# schemantic.net
KiCad netlist of a schematic drawn in EAGLE
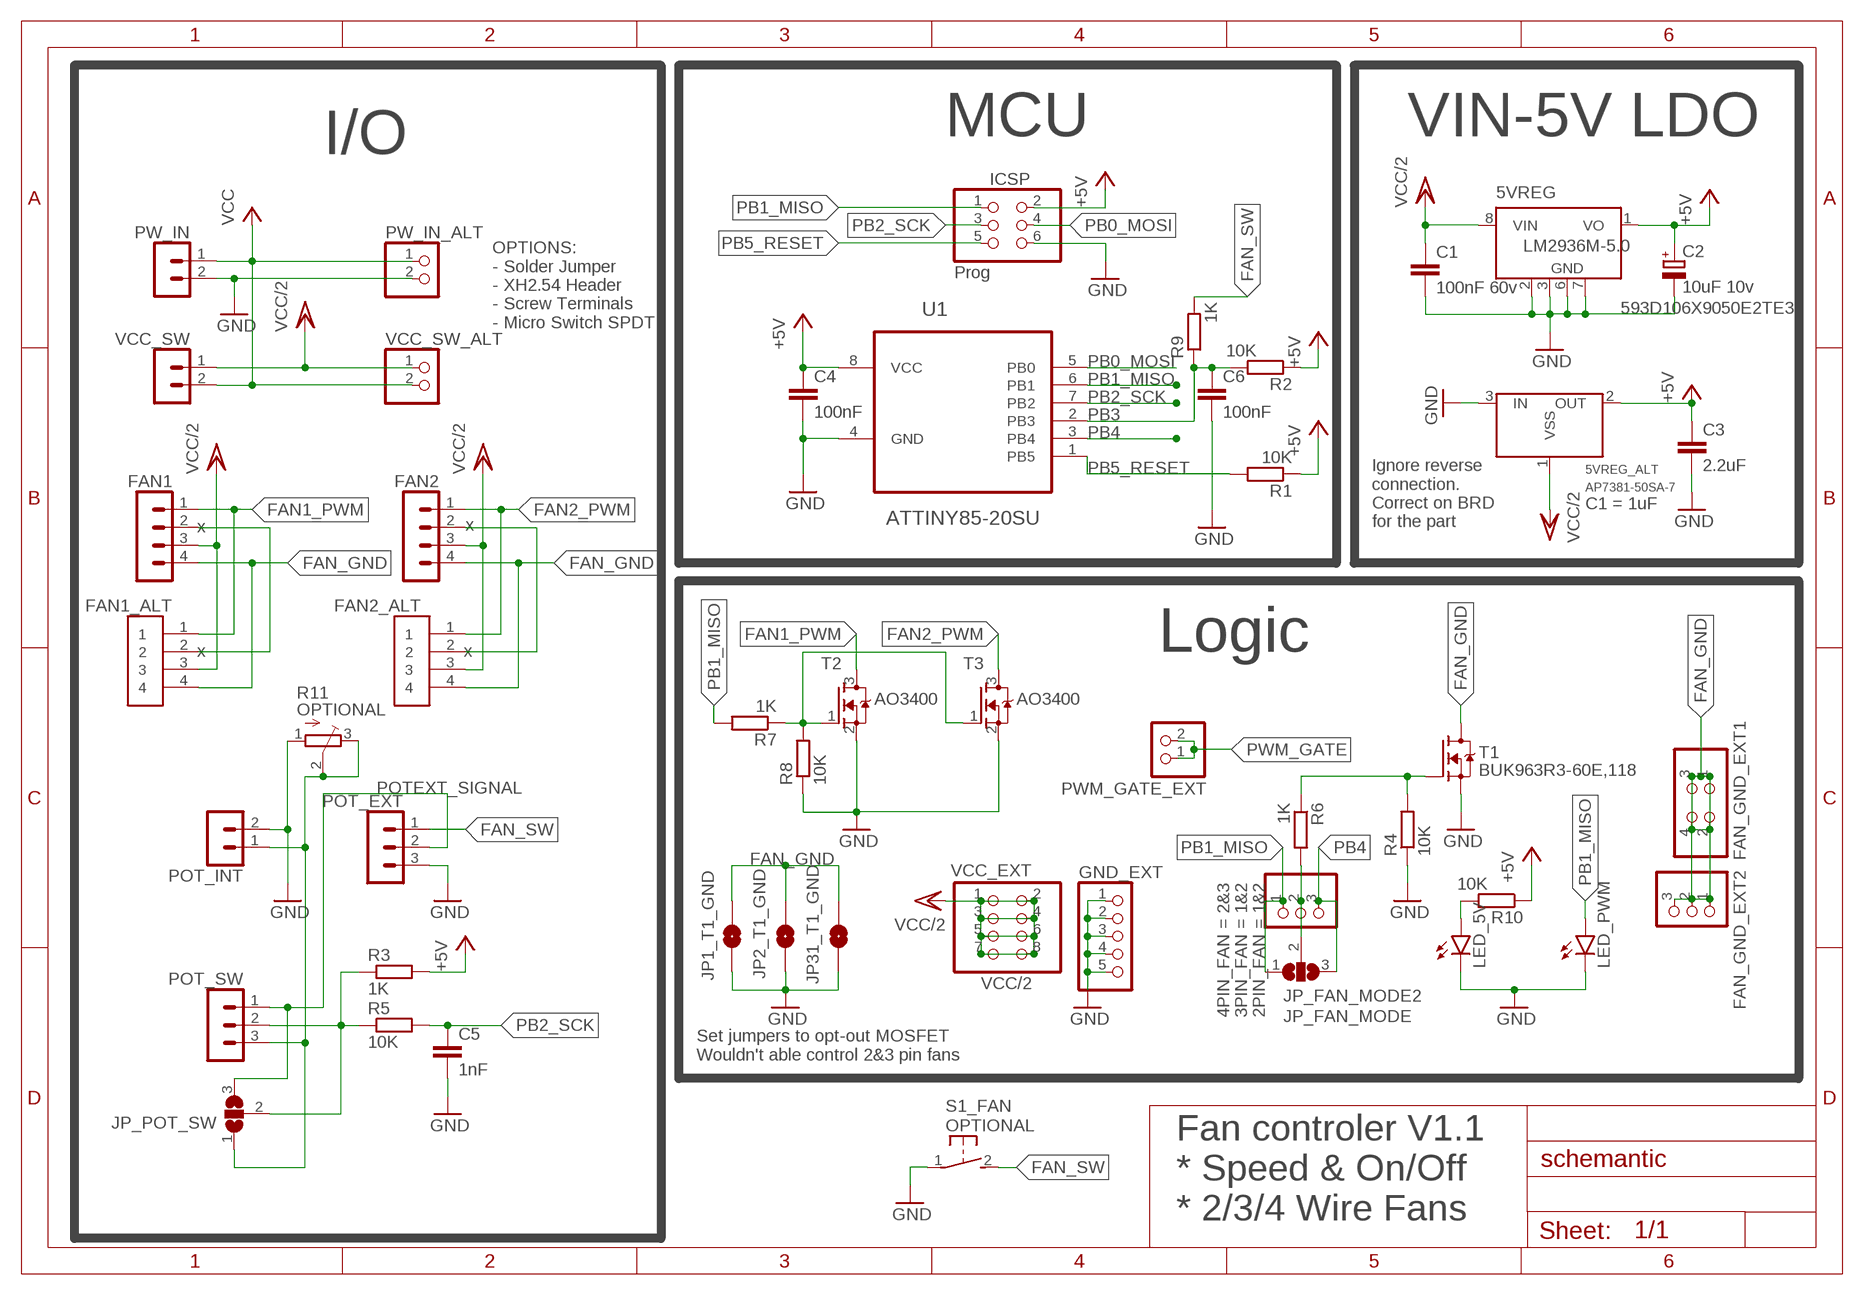
[diagram p0: schematic, sheet 1]

(export (version "E")
  (design (tool "Eeschema 10.0.6"))
  (components
    (comp (ref "5VREG")
      (value "LM2936M-5.0")
      (footprint "eagle-import:SO08")
      (fields
        (field (name "MF") "NATIONAL SEMICONDUCTOR")
        (field (name "MPN") "LM2936M-5.0/NOPB")
        (field (name "MPN_1") "LM2936HVMA-5.0/NOPB")
      )
      (libsource (lib "eagle-import") (part "LM2936M?-5.0"))
    )
    (comp (ref "5VREG_ALT")
      (value "AP7381-50SA-7")
      (footprint "eagle-import:XC6206_SOT-23")
      (fields (field (name "C1") "1uF"))
      (libsource (lib "eagle-import") (part "XC6206SOT-23"))
    )
    (comp (ref "C1")
      (value "100nF 60v")
      (footprint "eagle-import:C1206")
      (libsource (lib "eagle-import") (part "C-EUC1206"))
    )
    (comp (ref "C2")
      (value "10uF 10v")
      (footprint "eagle-import:SMC_E")
      (fields (field (name "MODEL") "593D106X9050E2TE3"))
      (libsource (lib "eagle-import") (part "CPOL-EUSMCE"))
    )
    (comp (ref "C3")
      (value "2.2uF")
      (footprint "eagle-import:C0805")
      (libsource (lib "eagle-import") (part "C-EUC0805"))
    )
    (comp (ref "C4")
      (value "100nF")
      (footprint "eagle-import:C0805")
      (libsource (lib "eagle-import") (part "C-EUC0805"))
    )
    (comp (ref "C5")
      (value "1nF")
      (footprint "eagle-import:C0805")
      (libsource (lib "eagle-import") (part "C-EUC0805"))
    )
    (comp (ref "C6")
      (value "100nF")
      (footprint "eagle-import:C0805")
      (libsource (lib "eagle-import") (part "C-EUC0805"))
    )
    (comp (ref "FAN1")
      (value "FAN1")
      (footprint "eagle-import:B4P-VH")
      (libsource (lib "eagle-import") (part "B4P-VH"))
    )
    (comp (ref "FAN1_ALT")
      (value "1X4-BIG")
      (footprint "eagle-import:1X04-BIG")
      (libsource (lib "eagle-import") (part "1X4-BIG"))
    )
    (comp (ref "FAN2")
      (value "FAN1")
      (footprint "eagle-import:B4P-VH")
      (libsource (lib "eagle-import") (part "B4P-VH"))
    )
    (comp (ref "FAN2_ALT")
      (value "1X4-BIG")
      (footprint "eagle-import:1X04-BIG")
      (libsource (lib "eagle-import") (part "1X4-BIG"))
    )
    (comp (ref "FAN_GND_EXT1")
      (value "PINHD-2X2")
      (footprint "eagle-import:2X02")
      (libsource (lib "eagle-import") (part "PINHD-2X2"))
    )
    (comp (ref "FAN_GND_EXT2")
      (value "PINHD-1X3")
      (footprint "eagle-import:1X03")
      (libsource (lib "eagle-import") (part "pinhead_PINHD-1X3"))
    )
    (comp (ref "GND_EXT")
      (value "PINHD-1X5")
      (footprint "eagle-import:1X05")
      (libsource (lib "eagle-import") (part "PINHD-1X5"))
    )
    (comp (ref "ICSP")
      (value "Prog")
      (footprint "eagle-import:2X03")
      (libsource (lib "eagle-import") (part "PINHD-2X3"))
    )
    (comp (ref "JP1_T1_GND")
      (value "JUMPER-SMT_2_NO_NO-SILK")
      (footprint "eagle-import:SMT-JUMPER_2_NO_NO-SILK")
      (libsource (lib "eagle-import") (part "JUMPER-SMT_2_NO_NO-SILK"))
    )
    (comp (ref "JP2_T1_GND")
      (value "JUMPER-SMT_2_NO_NO-SILK")
      (footprint "eagle-import:SMT-JUMPER_2_NO_NO-SILK")
      (libsource (lib "eagle-import") (part "JUMPER-SMT_2_NO_NO-SILK"))
    )
    (comp (ref "JP31_T1_GND")
      (value "JUMPER-SMT_2_NO_NO-SILK")
      (footprint "eagle-import:SMT-JUMPER_2_NO_NO-SILK")
      (libsource (lib "eagle-import") (part "JUMPER-SMT_2_NO_NO-SILK"))
    )
    (comp (ref "JP_FAN_MODE")
      (value "DC_COM_PWM")
      (footprint "eagle-import:SJ_2")
      (libsource (lib "eagle-import") (part "SJ2W"))
    )
    (comp (ref "JP_FAN_MODE2")
      (value "PINHD-1X3")
      (footprint "eagle-import:1X03")
      (fields (field (name "2PIN_FAN") "1&2") (field (name "3PIN_FAN") "1&2") (field (name "4PIN_FAN") "2&3"))
      (libsource (lib "eagle-import") (part "PINHD-1X3"))
    )
    (comp (ref "JP_POT_SW")
      (value "SJ2W")
      (footprint "eagle-import:SJ_2")
      (libsource (lib "eagle-import") (part "SJ2W"))
    )
    (comp (ref "LED_5V")
      (value "LEDCHIPLED_0805")
      (footprint "eagle-import:CHIPLED_0805")
      (libsource (lib "eagle-import") (part "LEDCHIPLED_0805"))
    )
    (comp (ref "LED_PWM")
      (value "LEDCHIPLED_0805")
      (footprint "eagle-import:CHIPLED_0805")
      (libsource (lib "eagle-import") (part "LEDCHIPLED_0805"))
    )
    (comp (ref "POT_EXT")
      (value "POT_EXT")
      (footprint "eagle-import:B3B-XH-A")
      (libsource (lib "eagle-import") (part "B3B-XH-2"))
    )
    (comp (ref "POT_INT")
      (value "POT_INT")
      (footprint "eagle-import:B2B-XH-A")
      (libsource (lib "eagle-import") (part "B2B-XH-2"))
    )
    (comp (ref "POT_SW")
      (value "POT_SW")
      (footprint "eagle-import:B3B-XH-A")
      (libsource (lib "eagle-import") (part "B3B-XH-2"))
    )
    (comp (ref "PWM_GATE_EXT")
      (value "PINHD-1X2")
      (footprint "eagle-import:1X02")
      (libsource (lib "eagle-import") (part "PINHD-1X2"))
    )
    (comp (ref "PW_IN")
      (value "Power In")
      (footprint "eagle-import:B2P-VH")
      (libsource (lib "eagle-import") (part "B2P-VH"))
    )
    (comp (ref "PW_IN_ALT")
      (value "PINHD-1X2")
      (footprint "eagle-import:1X02")
      (libsource (lib "eagle-import") (part "pinhead_325_PINHD-1X2"))
    )
    (comp (ref "R1")
      (value "10K")
      (footprint "eagle-import:R0805")
      (fields (field (name "SPICEPREFIX") "R"))
      (libsource (lib "eagle-import") (part "R-EU_R0805"))
    )
    (comp (ref "R2")
      (value "10K")
      (footprint "eagle-import:R0805")
      (fields (field (name "SPICEPREFIX") "R"))
      (libsource (lib "eagle-import") (part "R-EU_R0805"))
    )
    (comp (ref "R3")
      (value "1K")
      (footprint "eagle-import:R0805")
      (libsource (lib "eagle-import") (part "R-EU_R0805"))
    )
    (comp (ref "R4")
      (value "10K")
      (footprint "eagle-import:R0805")
      (fields (field (name "SPICEPREFIX") "R"))
      (libsource (lib "eagle-import") (part "R-EU_R0805"))
    )
    (comp (ref "R5")
      (value "10K")
      (footprint "eagle-import:R0805")
      (libsource (lib "eagle-import") (part "R-EU_R0805"))
    )
    (comp (ref "R6")
      (value "1K")
      (footprint "eagle-import:R0805")
      (fields (field (name "SPICEPREFIX") "R"))
      (libsource (lib "eagle-import") (part "R-EU_R0805"))
    )
    (comp (ref "R7")
      (value "1K")
      (footprint "eagle-import:R0805")
      (fields (field (name "SPICEPREFIX") "R"))
      (libsource (lib "eagle-import") (part "R-EU_R0805"))
    )
    (comp (ref "R8")
      (value "10K")
      (footprint "eagle-import:R0805")
      (fields (field (name "SPICEPREFIX") "R"))
      (libsource (lib "eagle-import") (part "R-EU_R0805"))
    )
    (comp (ref "R9")
      (value "1K")
      (footprint "eagle-import:R0805")
      (libsource (lib "eagle-import") (part "R-EU_R0805"))
    )
    (comp (ref "R10")
      (value "10K")
      (footprint "eagle-import:R0805")
      (libsource (lib "eagle-import") (part "R-EU_R0805"))
    )
    (comp (ref "R11")
      (value "TRIM_EU-3223W")
      (footprint "eagle-import:3223W")
      (libsource (lib "eagle-import") (part "TRIM_EU-3223W"))
    )
    (comp (ref "S1_FAN")
      (value "DTSM-3")
      (footprint "eagle-import:DTSM-3")
      (libsource (lib "eagle-import") (part "DTSM-3"))
    )
    (comp (ref "T1")
      (value "BUK963R3-60E,118")
      (footprint "eagle-import:D2PAK_TO263")
      (libsource (lib "eagle-import") (part "MOSFET-N-D2PAK"))
    )
    (comp (ref "T2")
      (value "AO3400")
      (footprint "eagle-import:SOT23")
      (fields (field (name "SPICEPREFIX") "J"))
      (libsource (lib "eagle-import") (part "MOSFET-NREFLOW"))
    )
    (comp (ref "T3")
      (value "AO3400")
      (footprint "eagle-import:SOT23")
      (fields (field (name "SPICEPREFIX") "J"))
      (libsource (lib "eagle-import") (part "MOSFET-NREFLOW"))
    )
    (comp (ref "U1")
      (value "ATTINY85-20SU")
      (footprint "eagle-import:SOIC127P798X216-8N")
      (libsource (lib "eagle-import") (part "ATTINY85-20SU"))
    )
    (comp (ref "VCC_EXT")
      (value "PINHD-2X4")
      (footprint "eagle-import:2X04")
      (libsource (lib "eagle-import") (part "PINHD-2X4"))
    )
    (comp (ref "VCC_SW")
      (value "Power SW")
      (footprint "eagle-import:B2P-VH")
      (libsource (lib "eagle-import") (part "B2P-VH"))
    )
    (comp (ref "VCC_SW_ALT")
      (value "PINHD-1X2")
      (footprint "eagle-import:1X02")
      (libsource (lib "eagle-import") (part "pinhead_325_PINHD-1X2"))
    )
  )
  (nets
    (net (code "1") (name "+5V") (class "Default")
      (node (ref "5VREG") (pin "1") (pinfunction "VO_1") (pintype "passive"))
      (node (ref "5VREG_ALT") (pin "2") (pinfunction "OUT_2") (pintype "bidirectional"))
      (node (ref "C2") (pin "+") (pinfunction "+_+") (pintype "passive"))
      (node (ref "C3") (pin "1") (pinfunction "1_1") (pintype "passive"))
      (node (ref "C4") (pin "1") (pinfunction "1_1") (pintype "passive"))
      (node (ref "ICSP") (pin "2") (pinfunction "2_2") (pintype "passive"))
      (node (ref "R1") (pin "1") (pinfunction "1_1") (pintype "passive"))
      (node (ref "R10") (pin "1") (pinfunction "1_1") (pintype "passive"))
      (node (ref "R2") (pin "1") (pinfunction "1_1") (pintype "passive"))
      (node (ref "R3") (pin "2") (pinfunction "2_2") (pintype "passive"))
      (node (ref "U1") (pin "8") (pinfunction "VCC_8") (pintype "power_in"))
    )
    (net (code "2") (name "/PB3") (class "Default")
      (node (ref "C6") (pin "1") (pinfunction "1_1") (pintype "passive"))
      (node (ref "R2") (pin "2") (pinfunction "2_2") (pintype "passive"))
      (node (ref "R9") (pin "1") (pinfunction "1_1") (pintype "passive"))
      (node (ref "U1") (pin "2") (pinfunction "PB3_2") (pintype "bidirectional"))
    )
    (net (code "3") (name "/POTEXT_SIGNAL") (class "Default")
      (node (ref "JP_POT_SW") (pin "3") (pinfunction "3_3") (pintype "passive"))
      (node (ref "POT_EXT") (pin "2") (pinfunction "2_2") (pintype "passive"))
      (node (ref "POT_SW") (pin "1") (pinfunction "1_1") (pintype "passive"))
    )
    (net (code "4") (name "FAN1_PWM") (class "Default")
      (node (ref "FAN1") (pin "1") (pinfunction "1_1") (pintype "passive"))
      (node (ref "FAN1_ALT") (pin "1") (pinfunction "1_1") (pintype "bidirectional"))
      (node (ref "T2") (pin "3") (pinfunction "D_3") (pintype "bidirectional"))
    )
    (net (code "5") (name "FAN2_PWM") (class "Default")
      (node (ref "FAN2") (pin "1") (pinfunction "1_1") (pintype "passive"))
      (node (ref "FAN2_ALT") (pin "1") (pinfunction "1_1") (pintype "bidirectional"))
      (node (ref "T3") (pin "3") (pinfunction "D_3") (pintype "bidirectional"))
    )
    (net (code "6") (name "FAN_GND") (class "Default")
      (node (ref "FAN1") (pin "4") (pinfunction "4_4") (pintype "passive"))
      (node (ref "FAN1_ALT") (pin "4") (pinfunction "4_4") (pintype "bidirectional"))
      (node (ref "FAN2") (pin "4") (pinfunction "4_4") (pintype "passive"))
      (node (ref "FAN2_ALT") (pin "4") (pinfunction "4_4") (pintype "bidirectional"))
      (node (ref "FAN_GND_EXT1") (pin "1") (pinfunction "1_1") (pintype "passive"))
      (node (ref "FAN_GND_EXT1") (pin "2") (pinfunction "2_2") (pintype "passive"))
      (node (ref "FAN_GND_EXT1") (pin "3") (pinfunction "3_3") (pintype "passive"))
      (node (ref "FAN_GND_EXT1") (pin "4") (pinfunction "4_4") (pintype "passive"))
      (node (ref "FAN_GND_EXT2") (pin "1") (pinfunction "1_1") (pintype "passive"))
      (node (ref "FAN_GND_EXT2") (pin "2") (pinfunction "2_2") (pintype "passive"))
      (node (ref "FAN_GND_EXT2") (pin "3") (pinfunction "3_3") (pintype "passive"))
      (node (ref "JP1_T1_GND") (pin "2") (pinfunction "2_2") (pintype "passive"))
      (node (ref "JP2_T1_GND") (pin "2") (pinfunction "2_2") (pintype "passive"))
      (node (ref "JP31_T1_GND") (pin "2") (pinfunction "2_2") (pintype "passive"))
      (node (ref "T1") (pin "2") (pinfunction "D_2") (pintype "passive"))
    )
    (net (code "7") (name "FAN_SW") (class "Default")
      (node (ref "POT_EXT") (pin "1") (pinfunction "1_1") (pintype "passive"))
      (node (ref "R9") (pin "2") (pinfunction "2_2") (pintype "passive"))
      (node (ref "S1_FAN") (pin "2") (pinfunction "2_2") (pintype "passive"))
    )
    (net (code "8") (name "GND") (class "Default")
      (node (ref "5VREG") (pin "2") (pinfunction "GND_2") (pintype "passive"))
      (node (ref "5VREG") (pin "3") (pinfunction "GND_3") (pintype "passive"))
      (node (ref "5VREG") (pin "6") (pinfunction "GND_6") (pintype "passive"))
      (node (ref "5VREG") (pin "7") (pinfunction "GND_7") (pintype "passive"))
      (node (ref "5VREG_ALT") (pin "3") (pinfunction "IN_3") (pintype "bidirectional"))
      (node (ref "C1") (pin "2") (pinfunction "2_2") (pintype "passive"))
      (node (ref "C2") (pin "-") (pinfunction "-_-") (pintype "passive"))
      (node (ref "C3") (pin "2") (pinfunction "2_2") (pintype "passive"))
      (node (ref "C4") (pin "2") (pinfunction "2_2") (pintype "passive"))
      (node (ref "C5") (pin "2") (pinfunction "2_2") (pintype "passive"))
      (node (ref "C6") (pin "2") (pinfunction "2_2") (pintype "passive"))
      (node (ref "GND_EXT") (pin "1") (pinfunction "1_1") (pintype "passive"))
      (node (ref "GND_EXT") (pin "2") (pinfunction "2_2") (pintype "passive"))
      (node (ref "GND_EXT") (pin "3") (pinfunction "3_3") (pintype "passive"))
      (node (ref "GND_EXT") (pin "4") (pinfunction "4_4") (pintype "passive"))
      (node (ref "GND_EXT") (pin "5") (pinfunction "5_5") (pintype "passive"))
      (node (ref "ICSP") (pin "6") (pinfunction "6_6") (pintype "passive"))
      (node (ref "JP1_T1_GND") (pin "1") (pinfunction "1_1") (pintype "passive"))
      (node (ref "JP2_T1_GND") (pin "1") (pinfunction "1_1") (pintype "passive"))
      (node (ref "JP31_T1_GND") (pin "1") (pinfunction "1_1") (pintype "passive"))
      (node (ref "LED_5V") (pin "C") (pinfunction "C_C") (pintype "passive"))
      (node (ref "LED_PWM") (pin "C") (pinfunction "C_C") (pintype "passive"))
      (node (ref "POT_EXT") (pin "3") (pinfunction "3_3") (pintype "passive"))
      (node (ref "POT_INT") (pin "2") (pinfunction "2_2") (pintype "passive"))
      (node (ref "PW_IN") (pin "2") (pinfunction "2_2") (pintype "passive"))
      (node (ref "PW_IN_ALT") (pin "2") (pinfunction "2_2") (pintype "passive"))
      (node (ref "R11") (pin "1") (pinfunction "A_1") (pintype "passive"))
      (node (ref "R4") (pin "1") (pinfunction "1_1") (pintype "passive"))
      (node (ref "R8") (pin "1") (pinfunction "1_1") (pintype "passive"))
      (node (ref "S1_FAN") (pin "1") (pinfunction "1_1") (pintype "passive"))
      (node (ref "T1") (pin "3") (pinfunction "S_3") (pintype "passive"))
      (node (ref "T2") (pin "2") (pinfunction "S_2") (pintype "bidirectional"))
      (node (ref "T3") (pin "2") (pinfunction "S_2") (pintype "bidirectional"))
      (node (ref "U1") (pin "4") (pinfunction "GND_4") (pintype "passive"))
    )
    (net (code "9") (name "Net-(FAN1-Pad2)") (class "Default")
      (node (ref "FAN1") (pin "2") (pinfunction "2_2") (pintype "passive"))
      (node (ref "FAN1_ALT") (pin "2") (pinfunction "2_2") (pintype "bidirectional"))
    )
    (net (code "10") (name "Net-(FAN2-Pad2)") (class "Default")
      (node (ref "FAN2") (pin "2") (pinfunction "2_2") (pintype "passive"))
      (node (ref "FAN2_ALT") (pin "2") (pinfunction "2_2") (pintype "bidirectional"))
    )
    (net (code "11") (name "Net-(JP_FAN_MODE-Pad2)") (class "Default")
      (node (ref "JP_FAN_MODE") (pin "2") (pinfunction "2_2") (pintype "passive"))
      (node (ref "JP_FAN_MODE2") (pin "2") (pinfunction "2_2") (pintype "passive"))
      (node (ref "R6") (pin "2") (pinfunction "2_2") (pintype "passive"))
    )
    (net (code "12") (name "Net-(JP_POT_SW-Pad2)") (class "Default")
      (node (ref "JP_POT_SW") (pin "2") (pinfunction "2_2") (pintype "passive"))
      (node (ref "POT_SW") (pin "2") (pinfunction "2_2") (pintype "passive"))
      (node (ref "R3") (pin "1") (pinfunction "1_1") (pintype "passive"))
      (node (ref "R5") (pin "1") (pinfunction "1_1") (pintype "passive"))
    )
    (net (code "13") (name "Net-(LED_5V-PadA)") (class "Default")
      (node (ref "LED_5V") (pin "A") (pinfunction "A_A") (pintype "passive"))
      (node (ref "R10") (pin "2") (pinfunction "2_2") (pintype "passive"))
    )
    (net (code "14") (name "Net-(R11-E)") (class "Default")
      (node (ref "JP_POT_SW") (pin "1") (pinfunction "1_1") (pintype "passive"))
      (node (ref "POT_INT") (pin "1") (pinfunction "1_1") (pintype "passive"))
      (node (ref "POT_SW") (pin "3") (pinfunction "3_3") (pintype "passive"))
      (node (ref "R11") (pin "2") (pinfunction "S_2") (pintype "passive"))
      (node (ref "R11") (pin "3") (pinfunction "E_3") (pintype "passive"))
    )
    (net (code "15") (name "Net-(T1-G)") (class "Default")
      (node (ref "R4") (pin "2") (pinfunction "2_2") (pintype "passive"))
      (node (ref "R6") (pin "1") (pinfunction "1_1") (pintype "passive"))
      (node (ref "T1") (pin "1") (pinfunction "G_1") (pintype "passive"))
    )
    (net (code "16") (name "PB0_MOSI") (class "Default")
      (node (ref "ICSP") (pin "4") (pinfunction "4_4") (pintype "passive"))
      (node (ref "U1") (pin "5") (pinfunction "PB0_5") (pintype "bidirectional"))
    )
    (net (code "17") (name "PB1_MISO") (class "Default")
      (node (ref "ICSP") (pin "1") (pinfunction "1_1") (pintype "passive"))
      (node (ref "JP_FAN_MODE") (pin "1") (pinfunction "1_1") (pintype "passive"))
      (node (ref "JP_FAN_MODE2") (pin "1") (pinfunction "1_1") (pintype "passive"))
      (node (ref "LED_PWM") (pin "A") (pinfunction "A_A") (pintype "passive"))
      (node (ref "R7") (pin "2") (pinfunction "2_2") (pintype "passive"))
      (node (ref "U1") (pin "6") (pinfunction "PB1_6") (pintype "bidirectional"))
    )
    (net (code "18") (name "PB2_SCK") (class "Default")
      (node (ref "C5") (pin "1") (pinfunction "1_1") (pintype "passive"))
      (node (ref "ICSP") (pin "3") (pinfunction "3_3") (pintype "passive"))
      (node (ref "R5") (pin "2") (pinfunction "2_2") (pintype "passive"))
      (node (ref "U1") (pin "7") (pinfunction "PB2_7") (pintype "bidirectional"))
    )
    (net (code "19") (name "PB4") (class "Default")
      (node (ref "JP_FAN_MODE") (pin "3") (pinfunction "3_3") (pintype "passive"))
      (node (ref "JP_FAN_MODE2") (pin "3") (pinfunction "3_3") (pintype "passive"))
      (node (ref "U1") (pin "3") (pinfunction "PB4_3") (pintype "bidirectional"))
    )
    (net (code "20") (name "PB5_RESET") (class "Default")
      (node (ref "ICSP") (pin "5") (pinfunction "5_5") (pintype "passive"))
      (node (ref "R1") (pin "2") (pinfunction "2_2") (pintype "passive"))
      (node (ref "U1") (pin "1") (pinfunction "PB5_1") (pintype "bidirectional"))
    )
    (net (code "21") (name "PWM_GATE") (class "Default")
      (node (ref "PWM_GATE_EXT") (pin "1") (pinfunction "1_1") (pintype "passive"))
      (node (ref "PWM_GATE_EXT") (pin "2") (pinfunction "2_2") (pintype "passive"))
      (node (ref "R7") (pin "1") (pinfunction "1_1") (pintype "passive"))
      (node (ref "R8") (pin "2") (pinfunction "2_2") (pintype "passive"))
      (node (ref "T2") (pin "1") (pinfunction "G_1") (pintype "bidirectional"))
      (node (ref "T3") (pin "1") (pinfunction "G_1") (pintype "bidirectional"))
    )
    (net (code "22") (name "VCC") (class "Default")
      (node (ref "PW_IN") (pin "1") (pinfunction "1_1") (pintype "passive"))
      (node (ref "PW_IN_ALT") (pin "1") (pinfunction "1_1") (pintype "passive"))
      (node (ref "VCC_SW") (pin "2") (pinfunction "2_2") (pintype "passive"))
      (node (ref "VCC_SW_ALT") (pin "2") (pinfunction "2_2") (pintype "passive"))
    )
    (net (code "23") (name "VCC{slash}2") (class "Default")
      (node (ref "5VREG") (pin "8") (pinfunction "VIN_8") (pintype "input"))
      (node (ref "5VREG_ALT") (pin "1") (pinfunction "VSS_1") (pintype "bidirectional"))
      (node (ref "C1") (pin "1") (pinfunction "1_1") (pintype "passive"))
      (node (ref "FAN1") (pin "3") (pinfunction "3_3") (pintype "passive"))
      (node (ref "FAN1_ALT") (pin "3") (pinfunction "3_3") (pintype "bidirectional"))
      (node (ref "FAN2") (pin "3") (pinfunction "3_3") (pintype "passive"))
      (node (ref "FAN2_ALT") (pin "3") (pinfunction "3_3") (pintype "bidirectional"))
      (node (ref "VCC_EXT") (pin "1") (pinfunction "1_1") (pintype "passive"))
      (node (ref "VCC_EXT") (pin "2") (pinfunction "2_2") (pintype "passive"))
      (node (ref "VCC_EXT") (pin "3") (pinfunction "3_3") (pintype "passive"))
      (node (ref "VCC_EXT") (pin "4") (pinfunction "4_4") (pintype "passive"))
      (node (ref "VCC_EXT") (pin "5") (pinfunction "5_5") (pintype "passive"))
      (node (ref "VCC_EXT") (pin "6") (pinfunction "6_6") (pintype "passive"))
      (node (ref "VCC_EXT") (pin "7") (pinfunction "7_7") (pintype "passive"))
      (node (ref "VCC_EXT") (pin "8") (pinfunction "8_8") (pintype "passive"))
      (node (ref "VCC_SW") (pin "1") (pinfunction "1_1") (pintype "passive"))
      (node (ref "VCC_SW_ALT") (pin "1") (pinfunction "1_1") (pintype "passive"))
    )
  )
)
